# AT_Guard_Simple_Main.net
KiCad netlist of a schematic drawn in Altium Designer
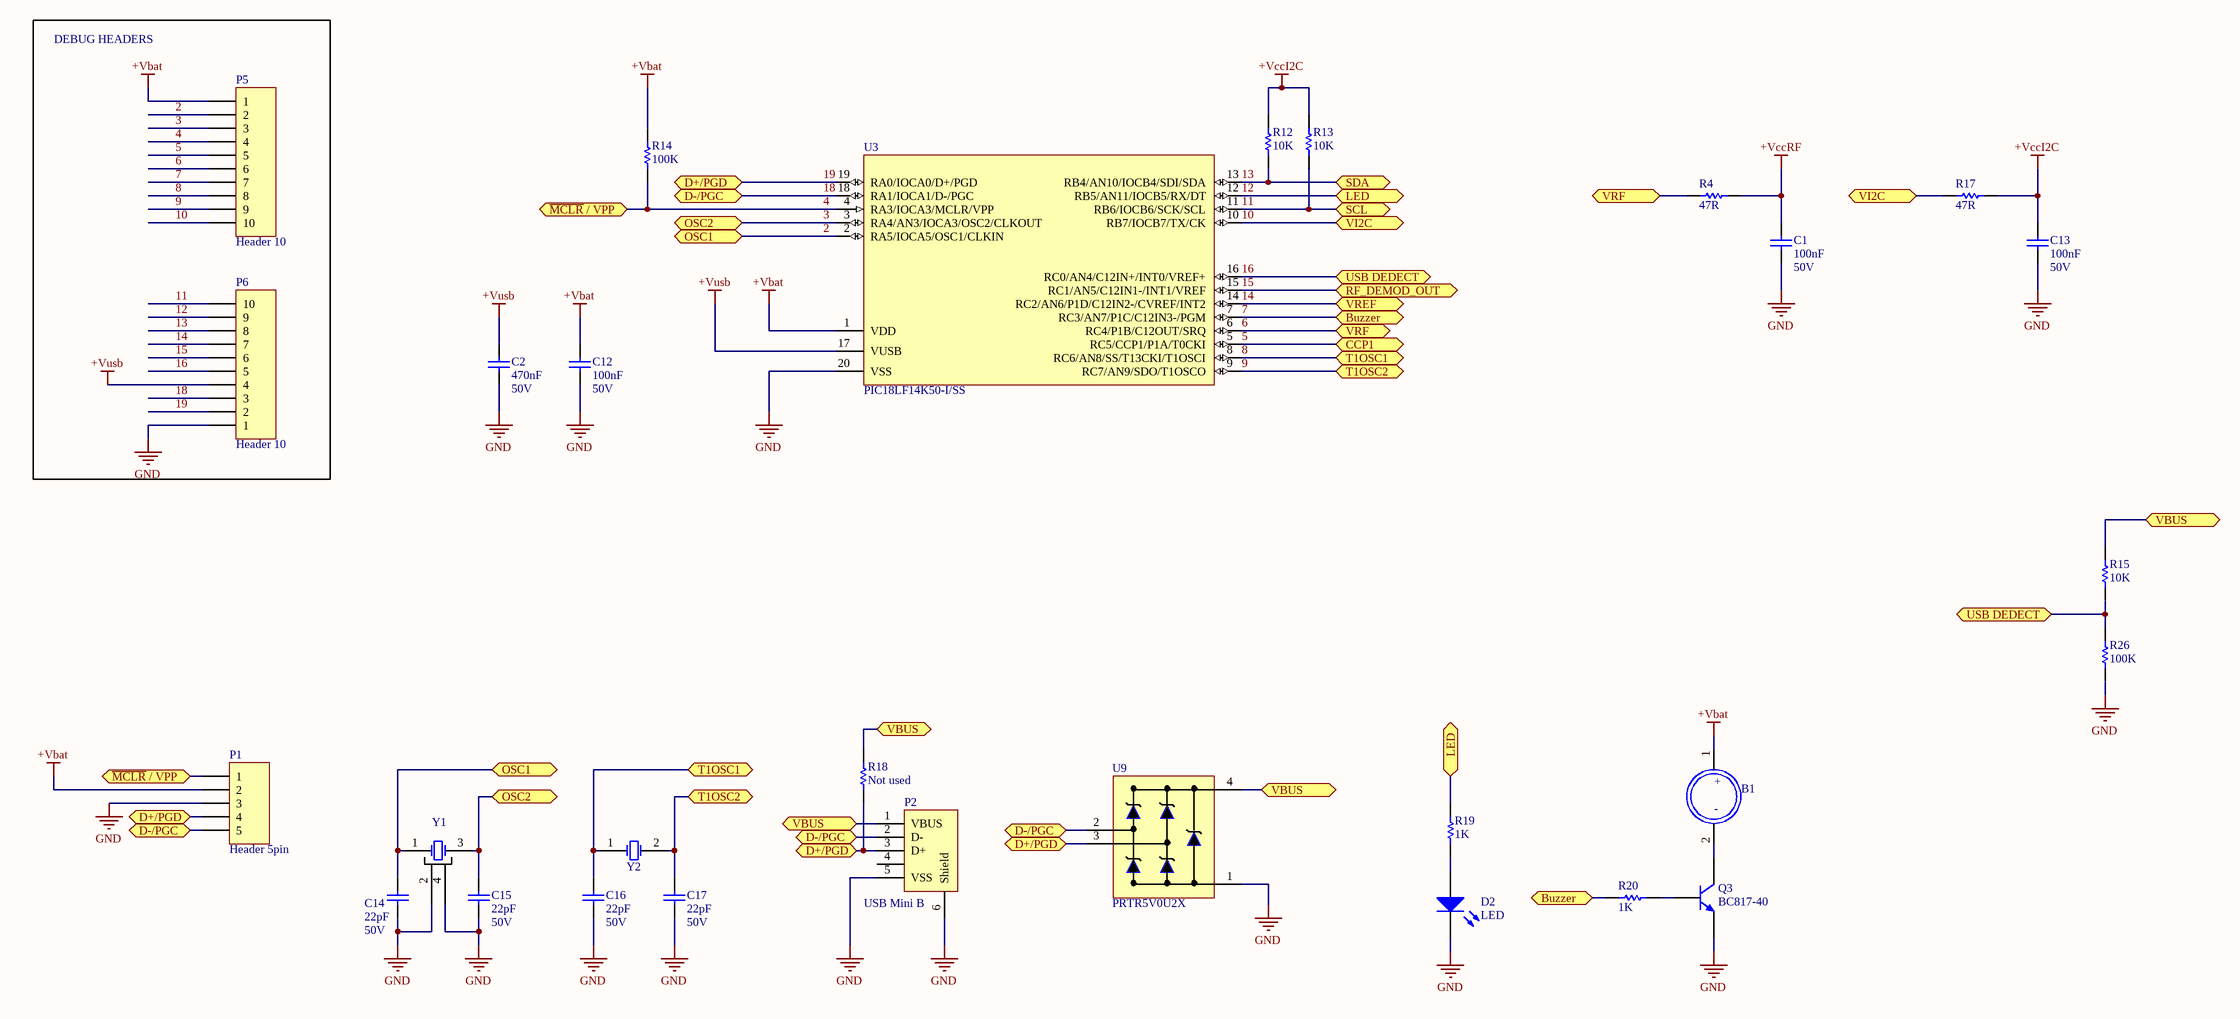
[diagram p0: AT Guard Simple Main.SchDoc]

(export (version "E")
  (design (tool "Eeschema 10.0.6"))
  (components
    (comp (ref "B1")
      (value "Buzzer 5V r=12mm, h=7.5 mm")
      (footprint "Buzzer 9x5.5 mm")
      (libsource (lib "Erdem_05112012") (part "Buzzer_"))
    )
    (comp (ref "C1")
      (value "100nF")
      (footprint "3-0603_N")
      (description "Capacitor")
      (fields
        (field (name "VOLTAGE") "50V")
        (field (name "Comment") "Cap")
        (field (name "PUBLISHER") "Altium Limited")
      )
      (libsource (lib "Erdem_05112012") (part "Cap"))
    )
    (comp (ref "C2")
      (value "470nF")
      (footprint "3-0603_L")
      (description "Capacitor")
      (fields
        (field (name "VOLTAGE") "50V")
        (field (name "Comment") "Cap")
        (field (name "PUBLISHER") "Altium Limited")
      )
      (libsource (lib "Erdem_05112012") (part "Cap"))
    )
    (comp (ref "C12")
      (value "100nF")
      (footprint "3-0603_L")
      (description "Capacitor")
      (fields
        (field (name "VOLTAGE") "50V")
        (field (name "Comment") "Cap")
        (field (name "PUBLISHER") "Altium Limited")
      )
      (libsource (lib "Erdem_05112012") (part "Cap"))
    )
    (comp (ref "C13")
      (value "100nF")
      (footprint "3-0603_L")
      (description "Capacitor")
      (fields
        (field (name "VOLTAGE") "50V")
        (field (name "Comment") "Cap")
        (field (name "PUBLISHER") "Altium Limited")
      )
      (libsource (lib "Erdem_05112012") (part "Cap"))
    )
    (comp (ref "C14")
      (value "22pF")
      (footprint "3-0603_L")
      (description "Capacitor")
      (fields
        (field (name "VOLTAGE") "50V")
        (field (name "Comment") "Cap")
        (field (name "PUBLISHER") "Altium Limited")
      )
      (libsource (lib "Erdem_05112012") (part "Cap"))
    )
    (comp (ref "C15")
      (value "22pF")
      (footprint "3-0603_L")
      (description "Capacitor")
      (fields
        (field (name "VOLTAGE") "50V")
        (field (name "Comment") "Cap")
        (field (name "PUBLISHER") "Altium Limited")
      )
      (libsource (lib "Erdem_05112012") (part "Cap"))
    )
    (comp (ref "C16")
      (value "22pF")
      (footprint "3-0603_L")
      (description "Capacitor")
      (fields
        (field (name "VOLTAGE") "50V")
        (field (name "Comment") "Cap")
        (field (name "PUBLISHER") "Altium Limited")
      )
      (libsource (lib "Erdem_05112012") (part "Cap"))
    )
    (comp (ref "C17")
      (value "22pF")
      (footprint "3-0603_L")
      (description "Capacitor")
      (fields
        (field (name "VOLTAGE") "50V")
        (field (name "Comment") "Cap")
        (field (name "PUBLISHER") "Altium Limited")
      )
      (libsource (lib "Erdem_05112012") (part "Cap"))
    )
    (comp (ref "D2")
      (value "LED")
      (footprint "6-0805 - LED")
      (description "Typical INFRARED GaAs LED")
      (fields (field (name "PUBLISHER") "Altium Limited"))
      (libsource (lib "Erdem_05112012") (part "LED"))
    )
    (comp (ref "P1")
      (value "Header 5pin")
      (footprint "Header 1.27mm 5P")
      (description "Header 5-Pin")
      (fields (field (name "PUBLISHER") "Altium Limited"))
      (libsource (lib "Erdem_05112012") (part "Header 5 pin"))
    )
    (comp (ref "P2")
      (value "USB Mini B")
      (footprint "USB Mini B Female_N 2")
      (fields (field (name "PUBLISHER") "Altium Limited"))
      (libsource (lib "Erdem_05112012") (part "USB Mini B"))
    )
    (comp (ref "P5")
      (value "Header 10")
      (footprint "Header 1.27mm 10P")
      (description "Header, 10-Pin")
      (fields (field (name "PUBLISHER") "Altium Limited"))
      (libsource (lib "") (part "Header 10_1"))
    )
    (comp (ref "P6")
      (value "Header 10")
      (footprint "Header 1.27mm 10P")
      (description "Header, 10-Pin")
      (fields (field (name "PUBLISHER") "Altium Limited"))
      (libsource (lib "Erdem_05112012") (part "Header 10"))
    )
    (comp (ref "Q3")
      (value "BC817-40")
      (footprint "SOT23_N")
      (description "NPN General-purpose Transistor")
      (fields (field (name "PUBLISHER") "Altium Limited"))
      (libsource (lib "Erdem_05112012") (part "BC817-40"))
    )
    (comp (ref "R4")
      (value "47R")
      (footprint "3-0603_N")
      (description "Resistor")
      (fields (field (name "Comment") "Res1") (field (name "PUBLISHER") "Altium Limited"))
      (libsource (lib "Erdem_05112012") (part "Res1"))
    )
    (comp (ref "R12")
      (value "10K")
      (footprint "3-0603_L")
      (description "Resistor")
      (fields (field (name "Comment") "Res1") (field (name "PUBLISHER") "Altium Limited"))
      (libsource (lib "Erdem_05112012") (part "Res1"))
    )
    (comp (ref "R13")
      (value "10K")
      (footprint "3-0603_L")
      (description "Resistor")
      (fields (field (name "Comment") "Res1") (field (name "PUBLISHER") "Altium Limited"))
      (libsource (lib "Erdem_05112012") (part "Res1"))
    )
    (comp (ref "R14")
      (value "100K")
      (footprint "3-0603_L")
      (description "Resistor")
      (fields (field (name "Comment") "Res1") (field (name "PUBLISHER") "Altium Limited"))
      (libsource (lib "Erdem_05112012") (part "Res1"))
    )
    (comp (ref "R15")
      (value "10K")
      (footprint "3-0603_L")
      (description "Resistor")
      (fields (field (name "Comment") "Res1") (field (name "PUBLISHER") "Altium Limited"))
      (libsource (lib "Erdem_05112012") (part "Res1"))
    )
    (comp (ref "R17")
      (value "47R")
      (footprint "3-0603_L")
      (description "Resistor")
      (fields (field (name "Comment") "Res1") (field (name "PUBLISHER") "Altium Limited"))
      (libsource (lib "Erdem_05112012") (part "Res1"))
    )
    (comp (ref "R18")
      (value "Not used")
      (footprint "3-0603_L")
      (description "Resistor")
      (fields (field (name "Comment") "Res1") (field (name "PUBLISHER") "Altium Limited"))
      (libsource (lib "Erdem_05112012") (part "Res1"))
    )
    (comp (ref "R19")
      (value "1K")
      (footprint "3-0603_L")
      (description "Resistor")
      (fields (field (name "Comment") "Res1") (field (name "PUBLISHER") "Altium Limited"))
      (libsource (lib "Erdem_05112012") (part "Res1"))
    )
    (comp (ref "R20")
      (value "1K")
      (footprint "3-0603_L")
      (description "Resistor")
      (fields (field (name "Comment") "Res1") (field (name "PUBLISHER") "Altium Limited"))
      (libsource (lib "Erdem_05112012") (part "Res1"))
    )
    (comp (ref "R26")
      (value "100K")
      (footprint "3-0603_L")
      (description "Resistor")
      (fields (field (name "Comment") "Res1") (field (name "PUBLISHER") "Altium Limited"))
      (libsource (lib "Erdem_05112012") (part "Res1"))
    )
    (comp (ref "U3")
      (value "PIC18LF14K50-I/SS")
      (footprint "SSOP-20")
      (fields (field (name "PUBLISHER") "Altium Limited"))
      (libsource (lib "Erdem_05112012") (part "PIC18LF14K50-I/SS"))
    )
    (comp (ref "U9")
      (value "PRTR5V0U2X")
      (footprint "SOT-143B")
      (description "Ultra low capacitance double rail-to-rail ESD protection diode")
      (fields (field (name "PUBLISHER") "Altium Limited"))
      (libsource (lib "Erdem_05112012") (part "PRTR5V0U2X"))
    )
    (comp (ref "Y1")
      (value "Crystal Oscillator")
      (footprint "4x2.5mm & 3.2x2.5 mm SMD CRYSTAL - duplicate")
      (fields (field (name "PUBLISHER") "Altium Limited"))
      (libsource (lib "Erdem_05112012") (part "Crystal Oscillator"))
    )
    (comp (ref "Y2")
      (value "XTAL_SMT")
      (footprint "32768 SMT 2.1x6.2mm Crystal")
      (description "Crystal Oscillator")
      (fields (field (name "PUBLISHER") "Altium Limited"))
      (libsource (lib "Erdem_05112012") (part "XTAL_SMT"))
    )
  )
  (nets
    (net (code "1") (name "+Vbat") (class "Default")
      (node (ref "B1") (pin "1") (pinfunction "1_1") (pintype "passive"))
      (node (ref "C12") (pin "2") (pinfunction "2_2") (pintype "passive"))
      (node (ref "P1") (pin "2") (pinfunction "2_2") (pintype "passive"))
      (node (ref "P5") (pin "1") (pinfunction "1_1") (pintype "passive"))
      (node (ref "R14") (pin "2") (pinfunction "2_2") (pintype "passive"))
      (node (ref "U3") (pin "1") (pinfunction "VDD_1") (pintype "power_in"))
    )
    (net (code "2") (name "+VccI2C") (class "Default")
      (node (ref "C13") (pin "2") (pinfunction "2_2") (pintype "passive"))
      (node (ref "R12") (pin "2") (pinfunction "2_2") (pintype "passive"))
      (node (ref "R13") (pin "2") (pinfunction "2_2") (pintype "passive"))
      (node (ref "R17") (pin "2") (pinfunction "2_2") (pintype "passive"))
    )
    (net (code "3") (name "+VccRF") (class "Default")
      (node (ref "C1") (pin "2") (pinfunction "2_2") (pintype "passive"))
      (node (ref "R4") (pin "2") (pinfunction "2_2") (pintype "passive"))
    )
    (net (code "4") (name "+Vusb") (class "Default")
      (node (ref "C2") (pin "2") (pinfunction "2_2") (pintype "passive"))
      (node (ref "P6") (pin "4") (pinfunction "4_4") (pintype "passive"))
      (node (ref "U3") (pin "17") (pinfunction "VUSB_17") (pintype "power_in"))
    )
    (net (code "5") (name "/2") (class "Default")
      (node (ref "C14") (pin "2") (pinfunction "2_2") (pintype "passive"))
      (node (ref "P5") (pin "2") (pinfunction "2_2") (pintype "passive"))
      (node (ref "U3") (pin "2") (pinfunction "RA5/IOCA5/OSC1/CLKIN_2") (pintype "bidirectional"))
      (node (ref "Y1") (pin "1") (pinfunction "OSC1_1") (pintype "passive"))
    )
    (net (code "6") (name "/3") (class "Default")
      (node (ref "C15") (pin "2") (pinfunction "2_2") (pintype "passive"))
      (node (ref "P5") (pin "3") (pinfunction "3_3") (pintype "passive"))
      (node (ref "U3") (pin "3") (pinfunction "RA4/AN3/IOCA3/OSC2/CLKOUT_3") (pintype "bidirectional"))
      (node (ref "Y1") (pin "3") (pinfunction "OSC2_3") (pintype "passive"))
    )
    (net (code "7") (name "/4") (class "Default")
      (node (ref "P1") (pin "1") (pinfunction "1_1") (pintype "passive"))
      (node (ref "P5") (pin "4") (pinfunction "4_4") (pintype "passive"))
      (node (ref "R14") (pin "1") (pinfunction "1_1") (pintype "passive"))
      (node (ref "U3") (pin "4") (pinfunction "RA3/IOCA3/MCLR/VPP_4") (pintype "input"))
    )
    (net (code "8") (name "/5") (class "Default")
      (node (ref "P5") (pin "5") (pinfunction "5_5") (pintype "passive"))
      (node (ref "U3") (pin "5") (pinfunction "RC5/CCP1/P1A/T0CKI_5") (pintype "bidirectional"))
    )
    (net (code "9") (name "/6") (class "Default")
      (node (ref "P5") (pin "6") (pinfunction "6_6") (pintype "passive"))
      (node (ref "R4") (pin "1") (pinfunction "1_1") (pintype "passive"))
      (node (ref "U3") (pin "6") (pinfunction "RC4/P1B/C12OUT/SRQ_6") (pintype "bidirectional"))
    )
    (net (code "10") (name "/7") (class "Default")
      (node (ref "P5") (pin "7") (pinfunction "7_7") (pintype "passive"))
      (node (ref "R20") (pin "2") (pinfunction "2_2") (pintype "passive"))
      (node (ref "U3") (pin "7") (pinfunction "RC3/AN7/P1C/C12IN3-/PGM_7") (pintype "bidirectional"))
    )
    (net (code "11") (name "/8") (class "Default")
      (node (ref "C16") (pin "2") (pinfunction "2_2") (pintype "passive"))
      (node (ref "P5") (pin "8") (pinfunction "8_8") (pintype "passive"))
      (node (ref "U3") (pin "8") (pinfunction "RC6/AN8/SS/T13CKI/T1OSCI_8") (pintype "bidirectional"))
      (node (ref "Y2") (pin "1") (pinfunction "OSC1_1") (pintype "passive"))
    )
    (net (code "12") (name "/9") (class "Default")
      (node (ref "C17") (pin "2") (pinfunction "2_2") (pintype "passive"))
      (node (ref "P5") (pin "9") (pinfunction "9_9") (pintype "passive"))
      (node (ref "U3") (pin "9") (pinfunction "RC7/AN9/SDO/T1OSCO_9") (pintype "bidirectional"))
      (node (ref "Y2") (pin "2") (pinfunction "OSC2_2") (pintype "passive"))
    )
    (net (code "13") (name "/10") (class "Default")
      (node (ref "P5") (pin "10") (pinfunction "10_10") (pintype "passive"))
      (node (ref "R17") (pin "1") (pinfunction "1_1") (pintype "passive"))
      (node (ref "U3") (pin "10") (pinfunction "RB7/IOCB7/TX/CK_10") (pintype "bidirectional"))
    )
    (net (code "14") (name "/11") (class "Default")
      (node (ref "P6") (pin "10") (pinfunction "10_10") (pintype "passive"))
      (node (ref "R13") (pin "1") (pinfunction "1_1") (pintype "passive"))
      (node (ref "U3") (pin "11") (pinfunction "RB6/IOCB6/SCK/SCL_11") (pintype "bidirectional"))
    )
    (net (code "15") (name "/12") (class "Default")
      (node (ref "P6") (pin "9") (pinfunction "9_9") (pintype "passive"))
      (node (ref "R19") (pin "2") (pinfunction "2_2") (pintype "passive"))
      (node (ref "U3") (pin "12") (pinfunction "RB5/AN11/IOCB5/RX/DT_12") (pintype "bidirectional"))
    )
    (net (code "16") (name "/13") (class "Default")
      (node (ref "P6") (pin "8") (pinfunction "8_8") (pintype "passive"))
      (node (ref "R12") (pin "1") (pinfunction "1_1") (pintype "passive"))
      (node (ref "U3") (pin "13") (pinfunction "RB4/AN10/IOCB4/SDI/SDA_13") (pintype "bidirectional"))
    )
    (net (code "17") (name "/14") (class "Default")
      (node (ref "P6") (pin "7") (pinfunction "7_7") (pintype "passive"))
      (node (ref "U3") (pin "14") (pinfunction "RC2/AN6/P1D/C12IN2-/CVREF/INT2_14") (pintype "bidirectional"))
    )
    (net (code "18") (name "/15") (class "Default")
      (node (ref "P6") (pin "6") (pinfunction "6_6") (pintype "passive"))
      (node (ref "U3") (pin "15") (pinfunction "RC1/AN5/C12IN1-/INT1/VREF_15") (pintype "bidirectional"))
    )
    (net (code "19") (name "/16") (class "Default")
      (node (ref "P6") (pin "5") (pinfunction "5_5") (pintype "passive"))
      (node (ref "R15") (pin "1") (pinfunction "1_1") (pintype "passive"))
      (node (ref "R26") (pin "2") (pinfunction "2_2") (pintype "passive"))
      (node (ref "U3") (pin "16") (pinfunction "RC0/AN4/C12IN+/INT0/VREF+_16") (pintype "bidirectional"))
    )
    (net (code "20") (name "/18") (class "Default")
      (node (ref "P1") (pin "5") (pinfunction "5_5") (pintype "passive"))
      (node (ref "P2") (pin "2") (pinfunction "D-_2") (pintype "passive"))
      (node (ref "P6") (pin "3") (pinfunction "3_3") (pintype "passive"))
      (node (ref "U3") (pin "18") (pinfunction "RA1/IOCA1/D-/PGC_18") (pintype "bidirectional"))
      (node (ref "U9") (pin "2") (pinfunction "2_2") (pintype "passive"))
    )
    (net (code "21") (name "/19") (class "Default")
      (node (ref "P1") (pin "4") (pinfunction "4_4") (pintype "passive"))
      (node (ref "P2") (pin "3") (pinfunction "D+_3") (pintype "passive"))
      (node (ref "P6") (pin "2") (pinfunction "2_2") (pintype "passive"))
      (node (ref "R18") (pin "1") (pinfunction "1_1") (pintype "passive"))
      (node (ref "U3") (pin "19") (pinfunction "RA0/IOCA0/D+/PGD_19") (pintype "bidirectional"))
      (node (ref "U9") (pin "3") (pinfunction "3_3") (pintype "passive"))
    )
    (net (code "22") (name "/VBUS") (class "Default")
      (node (ref "P2") (pin "1") (pinfunction "VBUS_1") (pintype "passive"))
      (node (ref "R15") (pin "2") (pinfunction "2_2") (pintype "passive"))
      (node (ref "R18") (pin "2") (pinfunction "2_2") (pintype "passive"))
      (node (ref "U9") (pin "4") (pinfunction "4_4") (pintype "passive"))
    )
    (net (code "23") (name "GND") (class "Default")
      (node (ref "C1") (pin "1") (pinfunction "1_1") (pintype "passive"))
      (node (ref "C12") (pin "1") (pinfunction "1_1") (pintype "passive"))
      (node (ref "C13") (pin "1") (pinfunction "1_1") (pintype "passive"))
      (node (ref "C14") (pin "1") (pinfunction "1_1") (pintype "passive"))
      (node (ref "C15") (pin "1") (pinfunction "1_1") (pintype "passive"))
      (node (ref "C16") (pin "1") (pinfunction "1_1") (pintype "passive"))
      (node (ref "C17") (pin "1") (pinfunction "1_1") (pintype "passive"))
      (node (ref "C2") (pin "1") (pinfunction "1_1") (pintype "passive"))
      (node (ref "D2") (pin "2") (pinfunction "K_2") (pintype "passive"))
      (node (ref "P1") (pin "3") (pinfunction "3_3") (pintype "passive"))
      (node (ref "P2") (pin "5") (pinfunction "VSS_5") (pintype "passive"))
      (node (ref "P2") (pin "6") (pinfunction "Shield_6") (pintype "passive"))
      (node (ref "P6") (pin "1") (pinfunction "1_1") (pintype "passive"))
      (node (ref "Q3") (pin "2") (pinfunction "E_2") (pintype "passive"))
      (node (ref "R26") (pin "1") (pinfunction "1_1") (pintype "passive"))
      (node (ref "U3") (pin "20") (pinfunction "VSS_20") (pintype "power_in"))
      (node (ref "U9") (pin "1") (pinfunction "1_1") (pintype "passive"))
      (node (ref "Y1") (pin "2") (pinfunction "GND_2") (pintype "power_in"))
      (node (ref "Y1") (pin "4") (pinfunction "GND_4") (pintype "power_in"))
    )
    (net (code "24") (name "Net-(D2-A)") (class "Default")
      (node (ref "D2") (pin "1") (pinfunction "A_1") (pintype "passive"))
      (node (ref "R19") (pin "1") (pinfunction "1_1") (pintype "passive"))
    )
    (net (code "25") (name "Net-(Q3-B)") (class "Default")
      (node (ref "Q3") (pin "1") (pinfunction "B_1") (pintype "passive"))
      (node (ref "R20") (pin "1") (pinfunction "1_1") (pintype "passive"))
    )
    (net (code "26") (name "Net-(Q3-C)") (class "Default")
      (node (ref "B1") (pin "2") (pinfunction "2_2") (pintype "passive"))
      (node (ref "Q3") (pin "3") (pinfunction "C_3") (pintype "passive"))
    )
    (net (code "27") (name "unconnected-(P2-Pad4)") (class "Default")
      (node (ref "P2") (pin "4") (pinfunction "4_4") (pintype "passive"))
    )
  )
)
